# XT-03_Bit_Reducer.net
KiCad netlist of a schematic drawn in EAGLE
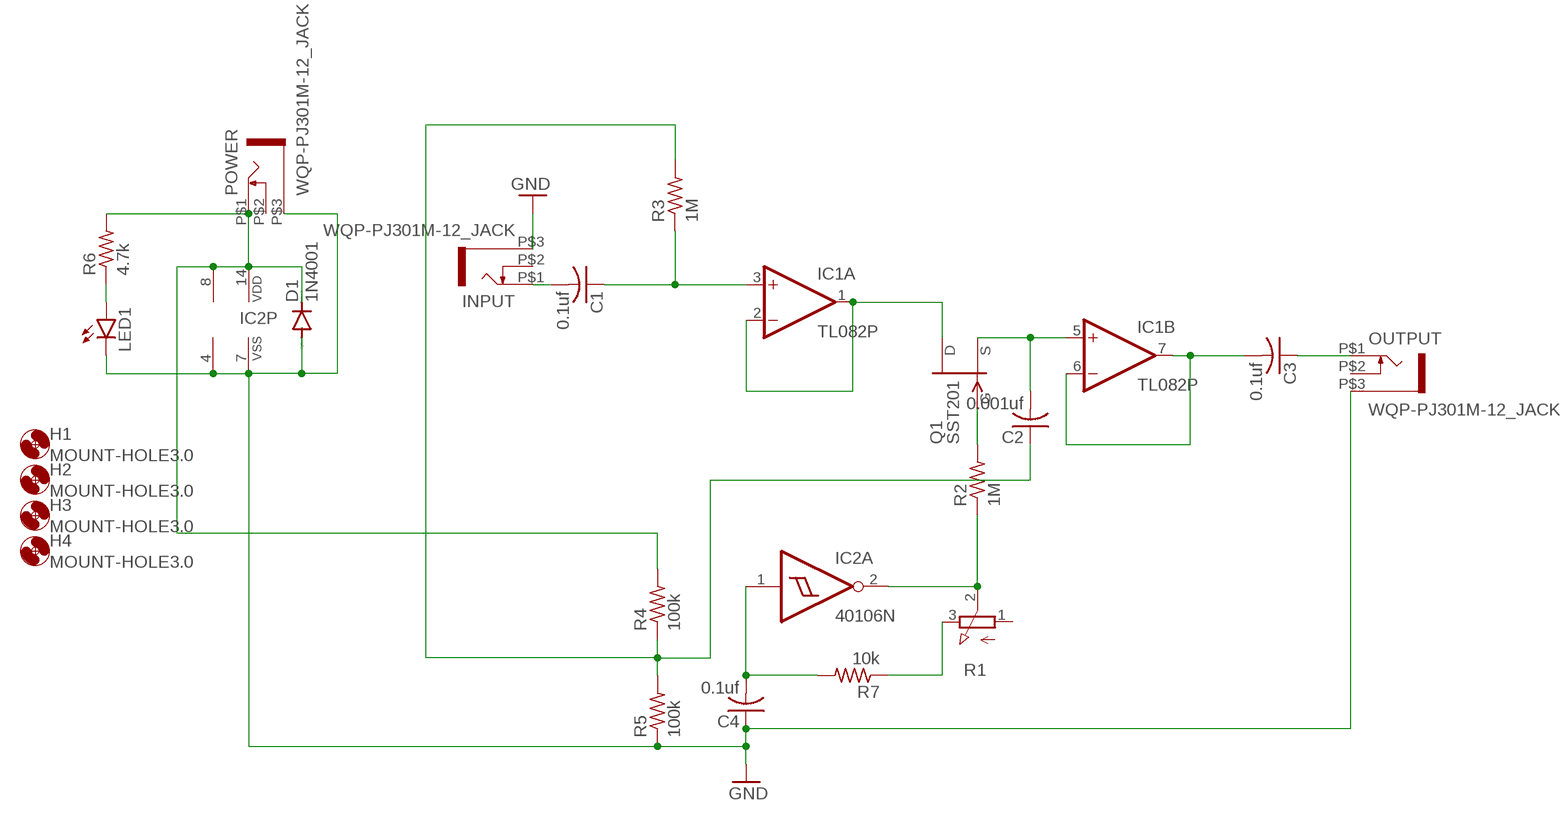
[diagram p0: schematic, sheet 1]

(export (version "E")
  (design (tool "Eeschema 10.0.6"))
  (components
    (comp (ref "C1")
      (value "0.1uf")
      (footprint "eagle-import:C050-025X075")
      (libsource (lib "eagle-import") (part "C-US050-025X075"))
    )
    (comp (ref "C2")
      (value "0.001uf")
      (footprint "eagle-import:C050-025X075")
      (libsource (lib "eagle-import") (part "C-US050-025X075"))
    )
    (comp (ref "C3")
      (value "0.1uf")
      (footprint "eagle-import:C050-025X075")
      (libsource (lib "eagle-import") (part "C-US050-025X075"))
    )
    (comp (ref "C4")
      (value "0.1uf")
      (footprint "eagle-import:C050-025X075")
      (libsource (lib "eagle-import") (part "C-US050-025X075"))
    )
    (comp (ref "D1")
      (value "1N4001")
      (footprint "eagle-import:DO41-10")
      (libsource (lib "eagle-import") (part "1N4004"))
    )
    (comp (ref "H1")
      (value "MOUNT-HOLE3.0")
      (footprint "eagle-import:3,0")
      (libsource (lib "eagle-import") (part "MOUNT-HOLE3.0"))
    )
    (comp (ref "H2")
      (value "MOUNT-HOLE3.0")
      (footprint "eagle-import:3,0")
      (libsource (lib "eagle-import") (part "MOUNT-HOLE3.0"))
    )
    (comp (ref "H3")
      (value "MOUNT-HOLE3.0")
      (footprint "eagle-import:3,0")
      (libsource (lib "eagle-import") (part "MOUNT-HOLE3.0"))
    )
    (comp (ref "H4")
      (value "MOUNT-HOLE3.0")
      (footprint "eagle-import:3,0")
      (libsource (lib "eagle-import") (part "MOUNT-HOLE3.0"))
    )
    (comp (ref "IC1")
      (value "TL082P")
      (footprint "eagle-import:DIL08")
      (libsource (lib "eagle-import") (part "TL082P"))
    )
    (comp (ref "IC2")
      (value "40106N")
      (footprint "eagle-import:DIL14")
      (libsource (lib "eagle-import") (part "40106N"))
    )
    (comp (ref "INPUT")
      (value "WQP-PJ301M-12_JACK")
      (footprint "eagle-import:WQP-PJ301M-12_JACK")
      (libsource (lib "eagle-import") (part "WQP-PJ301M-12_JACK"))
    )
    (comp (ref "LED1")
      (value "LED3MM")
      (footprint "eagle-import:LED3MM")
      (libsource (lib "eagle-import") (part "LED3MM"))
    )
    (comp (ref "OUTPUT")
      (value "WQP-PJ301M-12_JACK")
      (footprint "eagle-import:WQP-PJ301M-12_JACK")
      (libsource (lib "eagle-import") (part "WQP-PJ301M-12_JACK"))
    )
    (comp (ref "POWER")
      (value "WQP-PJ301M-12_JACK")
      (footprint "eagle-import:WQP-PJ301M-12_JACK")
      (libsource (lib "eagle-import") (part "WQP-PJ301M-12_JACK"))
    )
    (comp (ref "Q1")
      (value "SST201")
      (footprint "eagle-import:SOT23")
      (libsource (lib "eagle-import") (part "?20SST1"))
    )
    (comp (ref "R1")
      (value "EVUF2L")
      (footprint "eagle-import:EVUFXL")
      (libsource (lib "eagle-import") (part "EVULF2"))
    )
    (comp (ref "R2")
      (value "1M")
      (footprint "eagle-import:0207_7")
      (libsource (lib "eagle-import") (part "R-US_0207/7"))
    )
    (comp (ref "R3")
      (value "1M")
      (footprint "eagle-import:0207_7")
      (libsource (lib "eagle-import") (part "R-US_0207/7"))
    )
    (comp (ref "R4")
      (value "100k")
      (footprint "eagle-import:0207_7")
      (libsource (lib "eagle-import") (part "R-US_0207/7"))
    )
    (comp (ref "R5")
      (value "100k")
      (footprint "eagle-import:0207_7")
      (libsource (lib "eagle-import") (part "R-US_0207/7"))
    )
    (comp (ref "R6")
      (value "4.7k")
      (footprint "eagle-import:0207_7")
      (libsource (lib "eagle-import") (part "R-US_0207/7"))
    )
    (comp (ref "R7")
      (value "10k")
      (footprint "eagle-import:0207_7")
      (libsource (lib "eagle-import") (part "R-US_0207/7"))
    )
  )
  (nets
    (net (code "1") (name "GND") (class "Default")
      (node (ref "C4") (pin "1") (pinfunction "1_1") (pintype "passive"))
      (node (ref "D1") (pin "A") (pinfunction "A_A") (pintype "passive"))
      (node (ref "IC1") (pin "4") (pinfunction "V-_4") (pintype "power_in"))
      (node (ref "IC2") (pin "7") (pinfunction "VSS_7") (pintype "power_in"))
      (node (ref "INPUT") (pin "P$3") (pinfunction "1_P$3") (pintype "passive"))
      (node (ref "LED1") (pin "K") (pinfunction "C_K") (pintype "passive"))
      (node (ref "OUTPUT") (pin "P$3") (pinfunction "1_P$3") (pintype "passive"))
      (node (ref "POWER") (pin "P$3") (pinfunction "1_P$3") (pintype "passive"))
      (node (ref "R5") (pin "1") (pinfunction "1_1") (pintype "passive"))
    )
    (net (code "2") (name "Net-(C2-Pad1)") (class "Default")
      (node (ref "C2") (pin "1") (pinfunction "1_1") (pintype "passive"))
      (node (ref "R3") (pin "2") (pinfunction "2_2") (pintype "passive"))
      (node (ref "R4") (pin "1") (pinfunction "1_1") (pintype "passive"))
      (node (ref "R5") (pin "2") (pinfunction "2_2") (pintype "passive"))
    )
    (net (code "3") (name "Net-(IC1A-+IN)") (class "Default")
      (node (ref "C1") (pin "1") (pinfunction "1_1") (pintype "passive"))
      (node (ref "IC1") (pin "3") (pinfunction "+IN_3") (pintype "input"))
      (node (ref "R3") (pin "1") (pinfunction "1_1") (pintype "passive"))
    )
    (net (code "4") (name "Net-(IC1A--IN)") (class "Default")
      (node (ref "IC1") (pin "1") (pinfunction "OUT_1") (pintype "output"))
      (node (ref "IC1") (pin "2") (pinfunction "-IN_2") (pintype "input"))
      (node (ref "Q1") (pin "1") (pinfunction "D_1") (pintype "passive"))
    )
    (net (code "5") (name "Net-(IC1B-+IN)") (class "Default")
      (node (ref "C2") (pin "2") (pinfunction "2_2") (pintype "passive"))
      (node (ref "IC1") (pin "5") (pinfunction "+IN_5") (pintype "input"))
      (node (ref "Q1") (pin "2") (pinfunction "S_2") (pintype "passive"))
    )
    (net (code "6") (name "Net-(IC1B--IN)") (class "Default")
      (node (ref "C3") (pin "2") (pinfunction "2_2") (pintype "passive"))
      (node (ref "IC1") (pin "6") (pinfunction "-IN_6") (pintype "input"))
      (node (ref "IC1") (pin "7") (pinfunction "OUT_7") (pintype "output"))
    )
    (net (code "7") (name "Net-(IC1C-V+)") (class "Default")
      (node (ref "D1") (pin "C") (pinfunction "C_C") (pintype "passive"))
      (node (ref "IC1") (pin "8") (pinfunction "V+_8") (pintype "power_in"))
      (node (ref "IC2") (pin "14") (pinfunction "VDD_14") (pintype "power_in"))
      (node (ref "POWER") (pin "P$1") (pinfunction "2_P$1") (pintype "passive"))
      (node (ref "R4") (pin "2") (pinfunction "2_2") (pintype "passive"))
      (node (ref "R6") (pin "2") (pinfunction "2_2") (pintype "passive"))
    )
    (net (code "8") (name "Net-(IC2A-I)") (class "Default")
      (node (ref "C4") (pin "2") (pinfunction "2_2") (pintype "passive"))
      (node (ref "IC2") (pin "1") (pinfunction "I_1") (pintype "input"))
      (node (ref "R7") (pin "2") (pinfunction "2_2") (pintype "passive"))
    )
    (net (code "9") (name "Net-(IC2A-O)") (class "Default")
      (node (ref "IC2") (pin "2") (pinfunction "O_2") (pintype "output"))
      (node (ref "R1") (pin "2") (pinfunction "S_2") (pintype "passive"))
      (node (ref "R2") (pin "1") (pinfunction "1_1") (pintype "passive"))
    )
    (net (code "10") (name "Net-(INPUT-2)") (class "Default")
      (node (ref "C1") (pin "2") (pinfunction "2_2") (pintype "passive"))
      (node (ref "INPUT") (pin "P$1") (pinfunction "2_P$1") (pintype "passive"))
    )
    (net (code "11") (name "Net-(LED1-PadA)") (class "Default")
      (node (ref "LED1") (pin "A") (pinfunction "A_A") (pintype "passive"))
      (node (ref "R6") (pin "1") (pinfunction "1_1") (pintype "passive"))
    )
    (net (code "12") (name "Net-(OUTPUT-2)") (class "Default")
      (node (ref "C3") (pin "1") (pinfunction "1_1") (pintype "passive"))
      (node (ref "OUTPUT") (pin "P$1") (pinfunction "2_P$1") (pintype "passive"))
    )
    (net (code "13") (name "Net-(Q1-G)") (class "Default")
      (node (ref "Q1") (pin "3") (pinfunction "G_3") (pintype "passive"))
      (node (ref "R2") (pin "2") (pinfunction "2_2") (pintype "passive"))
    )
    (net (code "14") (name "Net-(R1-E)") (class "Default")
      (node (ref "R1") (pin "3") (pinfunction "E_3") (pintype "passive"))
      (node (ref "R7") (pin "1") (pinfunction "1_1") (pintype "passive"))
    )
    (net (code "15") (name "unconnected-(INPUT-3-PadP$2)") (class "Default")
      (node (ref "INPUT") (pin "P$2") (pinfunction "3_P$2") (pintype "passive"))
    )
    (net (code "16") (name "unconnected-(OUTPUT-3-PadP$2)") (class "Default")
      (node (ref "OUTPUT") (pin "P$2") (pinfunction "3_P$2") (pintype "passive"))
    )
    (net (code "17") (name "unconnected-(POWER-3-PadP$2)") (class "Default")
      (node (ref "POWER") (pin "P$2") (pinfunction "3_P$2") (pintype "passive"))
    )
    (net (code "18") (name "unconnected-(R1-A-Pad1)") (class "Default")
      (node (ref "R1") (pin "1") (pinfunction "A_1") (pintype "passive"))
    )
  )
)
